# PL_DDR4.net
KiCad netlist of a schematic drawn in Altium Designer
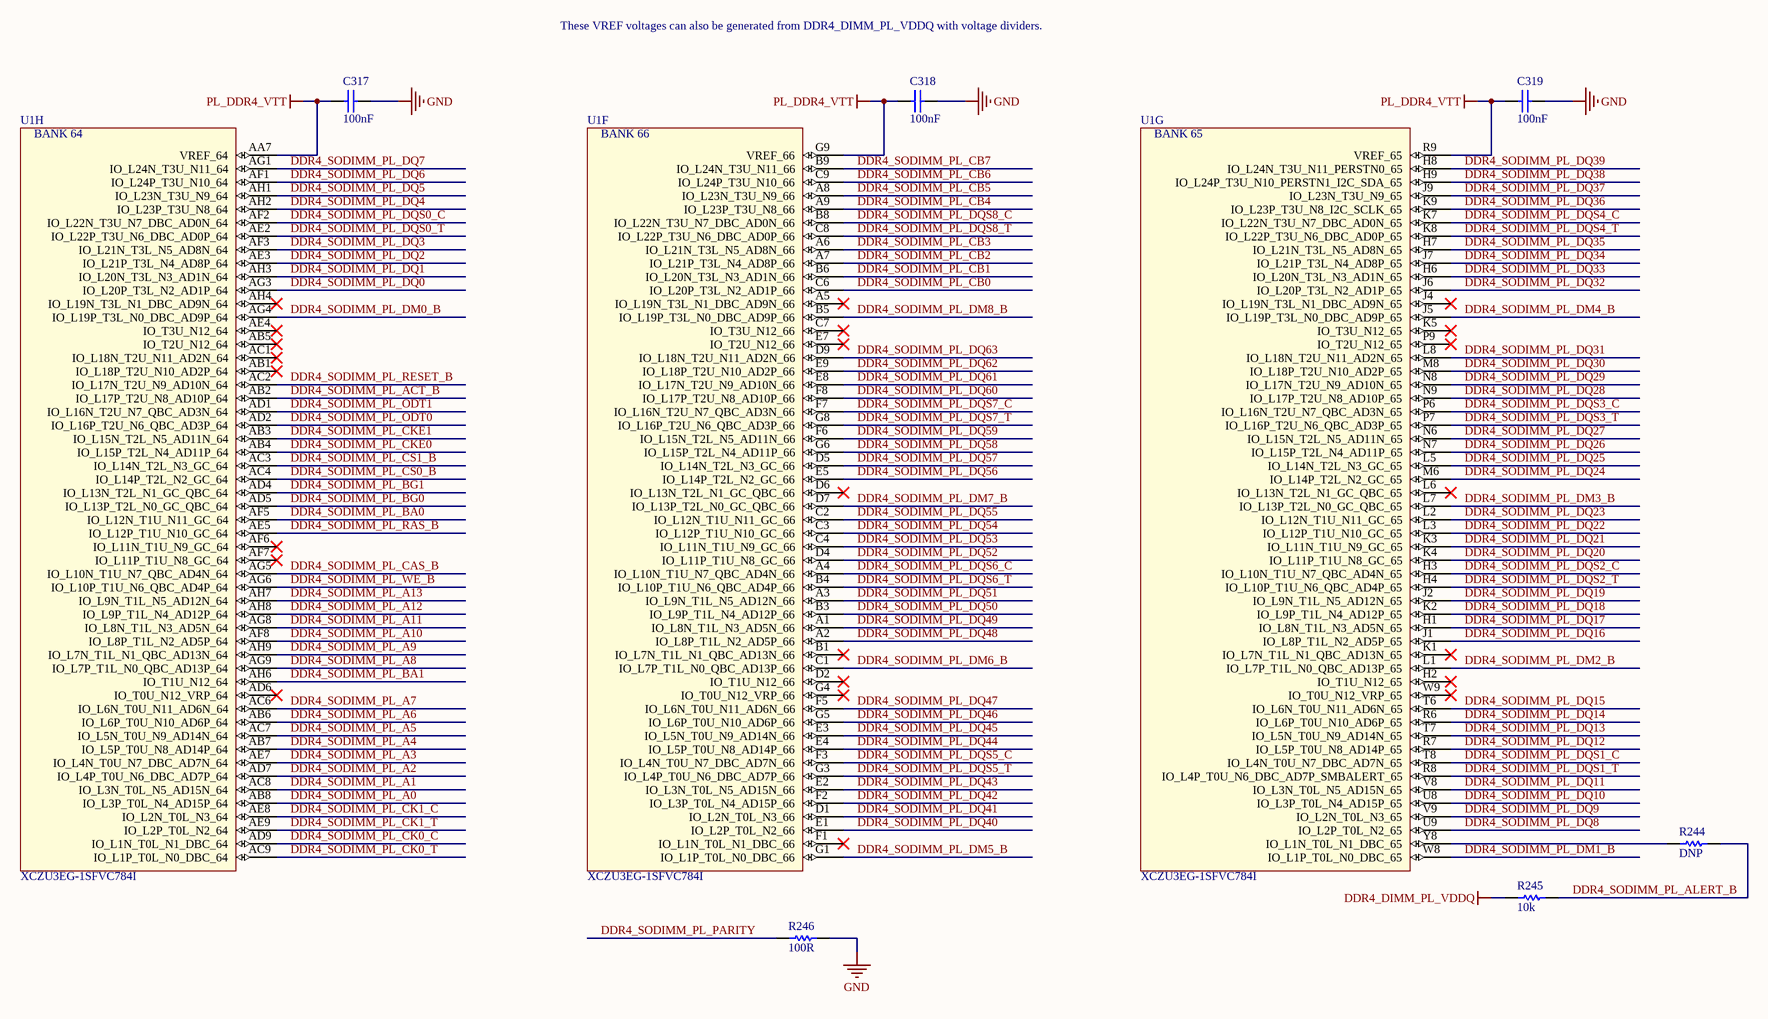
[diagram p0: PL_DDR4.SchDoc]

(export (version "E")
  (design (tool "Eeschema 10.0.6"))
  (components
    (comp (ref "C317")
      (value "100nF")
      (footprint "CAPC1005L_0402")
      (description "CAP CER 0.1UF 25V X7R 0402")
      (fields (field (name "VOLTAGE") "25V") (field (name "TOLERANCE") "10%"))
      (libsource (lib "Ultrascale_SchLib") (part "CAPCER0402X7R100N25V_10T"))
    )
    (comp (ref "C318")
      (value "100nF")
      (footprint "CAPC1005L_0402")
      (description "CAP CER 0.1UF 25V X7R 0402")
      (fields (field (name "VOLTAGE") "25V") (field (name "TOLERANCE") "10%"))
      (libsource (lib "Ultrascale_SchLib") (part "CAPCER0402X7R100N25V_10T"))
    )
    (comp (ref "C319")
      (value "100nF")
      (footprint "CAPC1005L_0402")
      (description "CAP CER 0.1UF 25V X7R 0402")
      (fields (field (name "VOLTAGE") "25V") (field (name "TOLERANCE") "10%"))
      (libsource (lib "Ultrascale_SchLib") (part "CAPCER0402X7R100N25V_10T"))
    )
    (comp (ref "R244")
      (value "DNP")
      (footprint "RESC1005L_0402")
      (description "RES SMD 0402 Footprint")
      (fields (field (name "Comment") "RES0402"))
      (libsource (lib "Ultrascale_SchLib") (part "RES0402"))
    )
    (comp (ref "R245")
      (value "10k")
      (footprint "RESC1005L_0402")
      (description "RES SMD 10K OHM 0.5% 1/16W 0402")
      (fields (field (name "POWER") "1/16W") (field (name "TOLERANCE") "0.5%"))
      (libsource (lib "Ultrascale_SchLib") (part "RES0402_10K_0W1_05T"))
    )
    (comp (ref "R246")
      (value "100R")
      (footprint "RESC1005L_0402")
      (description "RES SMD 100 OHM 1% 1/10W 0402")
      (fields (field (name "POWER") "1/10W") (field (name "TOLERANCE") "1%"))
      (libsource (lib "Ultrascale_SchLib") (part "RES0402_100R_0W1_1T"))
    )
    (comp (ref "U1")
      (value "XCZU3EG-1SFVC784I")
      (footprint "BGA784x28")
      (description "IC FPGA 252 I/O 784FCBGA - XILINX ZYNQ ULTRASCALE+")
      (libsource (lib "Ultrascale_SchLib") (part "XCZU3EG-1SFVC784I"))
    )
  )
  (nets
    (net (code "1") (name "/DDR4_SODIMM_PL_A0") (class "Default")
      (node (ref "U1") (pin "AB8") (pinfunction "IO_L3P_T0L_N4_AD15P_64_AB8") (pintype "bidirectional"))
    )
    (net (code "2") (name "/DDR4_SODIMM_PL_A1") (class "Default")
      (node (ref "U1") (pin "AC8") (pinfunction "IO_L3N_T0L_N5_AD15N_64_AC8") (pintype "bidirectional"))
    )
    (net (code "3") (name "/DDR4_SODIMM_PL_A2") (class "Default")
      (node (ref "U1") (pin "AD7") (pinfunction "IO_L4P_T0U_N6_DBC_AD7P_64_AD7") (pintype "bidirectional"))
    )
    (net (code "4") (name "/DDR4_SODIMM_PL_A3") (class "Default")
      (node (ref "U1") (pin "AE7") (pinfunction "IO_L4N_T0U_N7_DBC_AD7N_64_AE7") (pintype "bidirectional"))
    )
    (net (code "5") (name "/DDR4_SODIMM_PL_A4") (class "Default")
      (node (ref "U1") (pin "AB7") (pinfunction "IO_L5P_T0U_N8_AD14P_64_AB7") (pintype "bidirectional"))
    )
    (net (code "6") (name "/DDR4_SODIMM_PL_A5") (class "Default")
      (node (ref "U1") (pin "AC7") (pinfunction "IO_L5N_T0U_N9_AD14N_64_AC7") (pintype "bidirectional"))
    )
    (net (code "7") (name "/DDR4_SODIMM_PL_A6") (class "Default")
      (node (ref "U1") (pin "AB6") (pinfunction "IO_L6P_T0U_N10_AD6P_64_AB6") (pintype "bidirectional"))
    )
    (net (code "8") (name "/DDR4_SODIMM_PL_A7") (class "Default")
      (node (ref "U1") (pin "AC6") (pinfunction "IO_L6N_T0U_N11_AD6N_64_AC6") (pintype "bidirectional"))
    )
    (net (code "9") (name "/DDR4_SODIMM_PL_A8") (class "Default")
      (node (ref "U1") (pin "AG9") (pinfunction "IO_L7P_T1L_N0_QBC_AD13P_64_AG9") (pintype "bidirectional"))
    )
    (net (code "10") (name "/DDR4_SODIMM_PL_A9") (class "Default")
      (node (ref "U1") (pin "AH9") (pinfunction "IO_L7N_T1L_N1_QBC_AD13N_64_AH9") (pintype "bidirectional"))
    )
    (net (code "11") (name "/DDR4_SODIMM_PL_A10") (class "Default")
      (node (ref "U1") (pin "AF8") (pinfunction "IO_L8P_T1L_N2_AD5P_64_AF8") (pintype "bidirectional"))
    )
    (net (code "12") (name "/DDR4_SODIMM_PL_A11") (class "Default")
      (node (ref "U1") (pin "AG8") (pinfunction "IO_L8N_T1L_N3_AD5N_64_AG8") (pintype "bidirectional"))
    )
    (net (code "13") (name "/DDR4_SODIMM_PL_A12") (class "Default")
      (node (ref "U1") (pin "AH8") (pinfunction "IO_L9P_T1L_N4_AD12P_64_AH8") (pintype "bidirectional"))
    )
    (net (code "14") (name "/DDR4_SODIMM_PL_A13") (class "Default")
      (node (ref "U1") (pin "AH7") (pinfunction "IO_L9N_T1L_N5_AD12N_64_AH7") (pintype "bidirectional"))
    )
    (net (code "15") (name "/DDR4_SODIMM_PL_ACT_B") (class "Default")
      (node (ref "U1") (pin "AB2") (pinfunction "IO_L17P_T2U_N8_AD10P_64_AB2") (pintype "bidirectional"))
    )
    (net (code "16") (name "/DDR4_SODIMM_PL_ALERT_B") (class "Default")
      (node (ref "R244") (pin "2") (pinfunction "2_2") (pintype "passive"))
      (node (ref "R245") (pin "1") (pinfunction "1_1") (pintype "passive"))
    )
    (net (code "17") (name "/DDR4_SODIMM_PL_BA0") (class "Default")
      (node (ref "U1") (pin "AF5") (pinfunction "IO_L12N_T1U_N11_GC_64_AF5") (pintype "bidirectional"))
    )
    (net (code "18") (name "/DDR4_SODIMM_PL_BA1") (class "Default")
      (node (ref "U1") (pin "AH6") (pinfunction "IO_T1U_N12_64_AH6") (pintype "bidirectional"))
    )
    (net (code "19") (name "/DDR4_SODIMM_PL_BG0") (class "Default")
      (node (ref "U1") (pin "AD5") (pinfunction "IO_L13P_T2L_N0_GC_QBC_64_AD5") (pintype "bidirectional"))
    )
    (net (code "20") (name "/DDR4_SODIMM_PL_BG1") (class "Default")
      (node (ref "U1") (pin "AD4") (pinfunction "IO_L13N_T2L_N1_GC_QBC_64_AD4") (pintype "bidirectional"))
    )
    (net (code "21") (name "/DDR4_SODIMM_PL_CAS_B") (class "Default")
      (node (ref "U1") (pin "AG5") (pinfunction "IO_L10N_T1U_N7_QBC_AD4N_64_AG5") (pintype "bidirectional"))
    )
    (net (code "22") (name "/DDR4_SODIMM_PL_CB0") (class "Default")
      (node (ref "U1") (pin "C6") (pinfunction "IO_L20P_T3L_N2_AD1P_66_C6") (pintype "bidirectional"))
    )
    (net (code "23") (name "/DDR4_SODIMM_PL_CB1") (class "Default")
      (node (ref "U1") (pin "B6") (pinfunction "IO_L20N_T3L_N3_AD1N_66_B6") (pintype "bidirectional"))
    )
    (net (code "24") (name "/DDR4_SODIMM_PL_CB2") (class "Default")
      (node (ref "U1") (pin "A7") (pinfunction "IO_L21P_T3L_N4_AD8P_66_A7") (pintype "bidirectional"))
    )
    (net (code "25") (name "/DDR4_SODIMM_PL_CB3") (class "Default")
      (node (ref "U1") (pin "A6") (pinfunction "IO_L21N_T3L_N5_AD8N_66_A6") (pintype "bidirectional"))
    )
    (net (code "26") (name "/DDR4_SODIMM_PL_CB4") (class "Default")
      (node (ref "U1") (pin "A9") (pinfunction "IO_L23P_T3U_N8_66_A9") (pintype "bidirectional"))
    )
    (net (code "27") (name "/DDR4_SODIMM_PL_CB5") (class "Default")
      (node (ref "U1") (pin "A8") (pinfunction "IO_L23N_T3U_N9_66_A8") (pintype "bidirectional"))
    )
    (net (code "28") (name "/DDR4_SODIMM_PL_CB6") (class "Default")
      (node (ref "U1") (pin "C9") (pinfunction "IO_L24P_T3U_N10_66_C9") (pintype "bidirectional"))
    )
    (net (code "29") (name "/DDR4_SODIMM_PL_CB7") (class "Default")
      (node (ref "U1") (pin "B9") (pinfunction "IO_L24N_T3U_N11_66_B9") (pintype "bidirectional"))
    )
    (net (code "30") (name "/DDR4_SODIMM_PL_CK0_C") (class "Default")
      (node (ref "U1") (pin "AD9") (pinfunction "IO_L1N_T0L_N1_DBC_64_AD9") (pintype "bidirectional"))
    )
    (net (code "31") (name "/DDR4_SODIMM_PL_CK0_T") (class "Default")
      (node (ref "U1") (pin "AC9") (pinfunction "IO_L1P_T0L_N0_DBC_64_AC9") (pintype "bidirectional"))
    )
    (net (code "32") (name "/DDR4_SODIMM_PL_CK1_C") (class "Default")
      (node (ref "U1") (pin "AE8") (pinfunction "IO_L2N_T0L_N3_64_AE8") (pintype "bidirectional"))
    )
    (net (code "33") (name "/DDR4_SODIMM_PL_CK1_T") (class "Default")
      (node (ref "U1") (pin "AE9") (pinfunction "IO_L2P_T0L_N2_64_AE9") (pintype "bidirectional"))
    )
    (net (code "34") (name "/DDR4_SODIMM_PL_CKE0") (class "Default")
      (node (ref "U1") (pin "AB4") (pinfunction "IO_L15P_T2L_N4_AD11P_64_AB4") (pintype "bidirectional"))
    )
    (net (code "35") (name "/DDR4_SODIMM_PL_CKE1") (class "Default")
      (node (ref "U1") (pin "AB3") (pinfunction "IO_L15N_T2L_N5_AD11N_64_AB3") (pintype "bidirectional"))
    )
    (net (code "36") (name "/DDR4_SODIMM_PL_CS0_B") (class "Default")
      (node (ref "U1") (pin "AC4") (pinfunction "IO_L14P_T2L_N2_GC_64_AC4") (pintype "bidirectional"))
    )
    (net (code "37") (name "/DDR4_SODIMM_PL_CS1_B") (class "Default")
      (node (ref "U1") (pin "AC3") (pinfunction "IO_L14N_T2L_N3_GC_64_AC3") (pintype "bidirectional"))
    )
    (net (code "38") (name "/DDR4_SODIMM_PL_DM0_B") (class "Default")
      (node (ref "U1") (pin "AG4") (pinfunction "IO_L19P_T3L_N0_DBC_AD9P_64_AG4") (pintype "bidirectional"))
    )
    (net (code "39") (name "/DDR4_SODIMM_PL_DM1_B") (class "Default")
      (node (ref "U1") (pin "W8") (pinfunction "IO_L1P_T0L_N0_DBC_65_W8") (pintype "bidirectional"))
    )
    (net (code "40") (name "/DDR4_SODIMM_PL_DM2_B") (class "Default")
      (node (ref "U1") (pin "L1") (pinfunction "IO_L7P_T1L_N0_QBC_AD13P_65_L1") (pintype "bidirectional"))
    )
    (net (code "41") (name "/DDR4_SODIMM_PL_DM3_B") (class "Default")
      (node (ref "U1") (pin "L7") (pinfunction "IO_L13P_T2L_N0_GC_QBC_65_L7") (pintype "bidirectional"))
    )
    (net (code "42") (name "/DDR4_SODIMM_PL_DM4_B") (class "Default")
      (node (ref "U1") (pin "J5") (pinfunction "IO_L19P_T3L_N0_DBC_AD9P_65_J5") (pintype "bidirectional"))
    )
    (net (code "43") (name "/DDR4_SODIMM_PL_DM5_B") (class "Default")
      (node (ref "U1") (pin "G1") (pinfunction "IO_L1P_T0L_N0_DBC_66_G1") (pintype "bidirectional"))
    )
    (net (code "44") (name "/DDR4_SODIMM_PL_DM6_B") (class "Default")
      (node (ref "U1") (pin "C1") (pinfunction "IO_L7P_T1L_N0_QBC_AD13P_66_C1") (pintype "bidirectional"))
    )
    (net (code "45") (name "/DDR4_SODIMM_PL_DM7_B") (class "Default")
      (node (ref "U1") (pin "D7") (pinfunction "IO_L13P_T2L_N0_GC_QBC_66_D7") (pintype "bidirectional"))
    )
    (net (code "46") (name "/DDR4_SODIMM_PL_DM8_B") (class "Default")
      (node (ref "U1") (pin "B5") (pinfunction "IO_L19P_T3L_N0_DBC_AD9P_66_B5") (pintype "bidirectional"))
    )
    (net (code "47") (name "/DDR4_SODIMM_PL_DQ0") (class "Default")
      (node (ref "U1") (pin "AG3") (pinfunction "IO_L20P_T3L_N2_AD1P_64_AG3") (pintype "bidirectional"))
    )
    (net (code "48") (name "/DDR4_SODIMM_PL_DQ1") (class "Default")
      (node (ref "U1") (pin "AH3") (pinfunction "IO_L20N_T3L_N3_AD1N_64_AH3") (pintype "bidirectional"))
    )
    (net (code "49") (name "/DDR4_SODIMM_PL_DQ2") (class "Default")
      (node (ref "U1") (pin "AE3") (pinfunction "IO_L21P_T3L_N4_AD8P_64_AE3") (pintype "bidirectional"))
    )
    (net (code "50") (name "/DDR4_SODIMM_PL_DQ3") (class "Default")
      (node (ref "U1") (pin "AF3") (pinfunction "IO_L21N_T3L_N5_AD8N_64_AF3") (pintype "bidirectional"))
    )
    (net (code "51") (name "/DDR4_SODIMM_PL_DQ4") (class "Default")
      (node (ref "U1") (pin "AH2") (pinfunction "IO_L23P_T3U_N8_64_AH2") (pintype "bidirectional"))
    )
    (net (code "52") (name "/DDR4_SODIMM_PL_DQ5") (class "Default")
      (node (ref "U1") (pin "AH1") (pinfunction "IO_L23N_T3U_N9_64_AH1") (pintype "bidirectional"))
    )
    (net (code "53") (name "/DDR4_SODIMM_PL_DQ6") (class "Default")
      (node (ref "U1") (pin "AF1") (pinfunction "IO_L24P_T3U_N10_64_AF1") (pintype "bidirectional"))
    )
    (net (code "54") (name "/DDR4_SODIMM_PL_DQ7") (class "Default")
      (node (ref "U1") (pin "AG1") (pinfunction "IO_L24N_T3U_N11_64_AG1") (pintype "bidirectional"))
    )
    (net (code "55") (name "/DDR4_SODIMM_PL_DQ8") (class "Default")
      (node (ref "U1") (pin "U9") (pinfunction "IO_L2P_T0L_N2_65_U9") (pintype "bidirectional"))
    )
    (net (code "56") (name "/DDR4_SODIMM_PL_DQ9") (class "Default")
      (node (ref "U1") (pin "V9") (pinfunction "IO_L2N_T0L_N3_65_V9") (pintype "bidirectional"))
    )
    (net (code "57") (name "/DDR4_SODIMM_PL_DQ10") (class "Default")
      (node (ref "U1") (pin "U8") (pinfunction "IO_L3P_T0L_N4_AD15P_65_U8") (pintype "bidirectional"))
    )
    (net (code "58") (name "/DDR4_SODIMM_PL_DQ11") (class "Default")
      (node (ref "U1") (pin "V8") (pinfunction "IO_L3N_T0L_N5_AD15N_65_V8") (pintype "bidirectional"))
    )
    (net (code "59") (name "/DDR4_SODIMM_PL_DQ12") (class "Default")
      (node (ref "U1") (pin "R7") (pinfunction "IO_L5P_T0U_N8_AD14P_65_R7") (pintype "bidirectional"))
    )
    (net (code "60") (name "/DDR4_SODIMM_PL_DQ13") (class "Default")
      (node (ref "U1") (pin "T7") (pinfunction "IO_L5N_T0U_N9_AD14N_65_T7") (pintype "bidirectional"))
    )
    (net (code "61") (name "/DDR4_SODIMM_PL_DQ14") (class "Default")
      (node (ref "U1") (pin "R6") (pinfunction "IO_L6P_T0U_N10_AD6P_65_R6") (pintype "bidirectional"))
    )
    (net (code "62") (name "/DDR4_SODIMM_PL_DQ15") (class "Default")
      (node (ref "U1") (pin "T6") (pinfunction "IO_L6N_T0U_N11_AD6N_65_T6") (pintype "bidirectional"))
    )
    (net (code "63") (name "/DDR4_SODIMM_PL_DQ16") (class "Default")
      (node (ref "U1") (pin "J1") (pinfunction "IO_L8P_T1L_N2_AD5P_65_J1") (pintype "bidirectional"))
    )
    (net (code "64") (name "/DDR4_SODIMM_PL_DQ17") (class "Default")
      (node (ref "U1") (pin "H1") (pinfunction "IO_L8N_T1L_N3_AD5N_65_H1") (pintype "bidirectional"))
    )
    (net (code "65") (name "/DDR4_SODIMM_PL_DQ18") (class "Default")
      (node (ref "U1") (pin "K2") (pinfunction "IO_L9P_T1L_N4_AD12P_65_K2") (pintype "bidirectional"))
    )
    (net (code "66") (name "/DDR4_SODIMM_PL_DQ19") (class "Default")
      (node (ref "U1") (pin "J2") (pinfunction "IO_L9N_T1L_N5_AD12N_65_J2") (pintype "bidirectional"))
    )
    (net (code "67") (name "/DDR4_SODIMM_PL_DQ20") (class "Default")
      (node (ref "U1") (pin "K4") (pinfunction "IO_L11P_T1U_N8_GC_65_K4") (pintype "bidirectional"))
    )
    (net (code "68") (name "/DDR4_SODIMM_PL_DQ21") (class "Default")
      (node (ref "U1") (pin "K3") (pinfunction "IO_L11N_T1U_N9_GC_65_K3") (pintype "bidirectional"))
    )
    (net (code "69") (name "/DDR4_SODIMM_PL_DQ22") (class "Default")
      (node (ref "U1") (pin "L3") (pinfunction "IO_L12P_T1U_N10_GC_65_L3") (pintype "bidirectional"))
    )
    (net (code "70") (name "/DDR4_SODIMM_PL_DQ23") (class "Default")
      (node (ref "U1") (pin "L2") (pinfunction "IO_L12N_T1U_N11_GC_65_L2") (pintype "bidirectional"))
    )
    (net (code "71") (name "/DDR4_SODIMM_PL_DQ24") (class "Default")
      (node (ref "U1") (pin "M6") (pinfunction "IO_L14P_T2L_N2_GC_65_M6") (pintype "bidirectional"))
    )
    (net (code "72") (name "/DDR4_SODIMM_PL_DQ25") (class "Default")
      (node (ref "U1") (pin "L5") (pinfunction "IO_L14N_T2L_N3_GC_65_L5") (pintype "bidirectional"))
    )
    (net (code "73") (name "/DDR4_SODIMM_PL_DQ26") (class "Default")
      (node (ref "U1") (pin "N7") (pinfunction "IO_L15P_T2L_N4_AD11P_65_N7") (pintype "bidirectional"))
    )
    (net (code "74") (name "/DDR4_SODIMM_PL_DQ27") (class "Default")
      (node (ref "U1") (pin "N6") (pinfunction "IO_L15N_T2L_N5_AD11N_65_N6") (pintype "bidirectional"))
    )
    (net (code "75") (name "/DDR4_SODIMM_PL_DQ28") (class "Default")
      (node (ref "U1") (pin "N9") (pinfunction "IO_L17P_T2U_N8_AD10P_65_N9") (pintype "bidirectional"))
    )
    (net (code "76") (name "/DDR4_SODIMM_PL_DQ29") (class "Default")
      (node (ref "U1") (pin "N8") (pinfunction "IO_L17N_T2U_N9_AD10N_65_N8") (pintype "bidirectional"))
    )
    (net (code "77") (name "/DDR4_SODIMM_PL_DQ30") (class "Default")
      (node (ref "U1") (pin "M8") (pinfunction "IO_L18P_T2U_N10_AD2P_65_M8") (pintype "bidirectional"))
    )
    (net (code "78") (name "/DDR4_SODIMM_PL_DQ31") (class "Default")
      (node (ref "U1") (pin "L8") (pinfunction "IO_L18N_T2U_N11_AD2N_65_L8") (pintype "bidirectional"))
    )
    (net (code "79") (name "/DDR4_SODIMM_PL_DQ32") (class "Default")
      (node (ref "U1") (pin "J6") (pinfunction "IO_L20P_T3L_N2_AD1P_65_J6") (pintype "bidirectional"))
    )
    (net (code "80") (name "/DDR4_SODIMM_PL_DQ33") (class "Default")
      (node (ref "U1") (pin "H6") (pinfunction "IO_L20N_T3L_N3_AD1N_65_H6") (pintype "bidirectional"))
    )
    (net (code "81") (name "/DDR4_SODIMM_PL_DQ34") (class "Default")
      (node (ref "U1") (pin "J7") (pinfunction "IO_L21P_T3L_N4_AD8P_65_J7") (pintype "bidirectional"))
    )
    (net (code "82") (name "/DDR4_SODIMM_PL_DQ35") (class "Default")
      (node (ref "U1") (pin "H7") (pinfunction "IO_L21N_T3L_N5_AD8N_65_H7") (pintype "bidirectional"))
    )
    (net (code "83") (name "/DDR4_SODIMM_PL_DQ36") (class "Default")
      (node (ref "U1") (pin "K9") (pinfunction "IO_L23P_T3U_N8_I2C_SCLK_65_K9") (pintype "bidirectional"))
    )
    (net (code "84") (name "/DDR4_SODIMM_PL_DQ37") (class "Default")
      (node (ref "U1") (pin "J9") (pinfunction "IO_L23N_T3U_N9_65_J9") (pintype "bidirectional"))
    )
    (net (code "85") (name "/DDR4_SODIMM_PL_DQ38") (class "Default")
      (node (ref "U1") (pin "H9") (pinfunction "IO_L24P_T3U_N10_PERSTN1_I2C_SDA_65_H9") (pintype "bidirectional"))
    )
    (net (code "86") (name "/DDR4_SODIMM_PL_DQ39") (class "Default")
      (node (ref "U1") (pin "H8") (pinfunction "IO_L24N_T3U_N11_PERSTN0_65_H8") (pintype "bidirectional"))
    )
    (net (code "87") (name "/DDR4_SODIMM_PL_DQ40") (class "Default")
      (node (ref "U1") (pin "E1") (pinfunction "IO_L2P_T0L_N2_66_E1") (pintype "bidirectional"))
    )
    (net (code "88") (name "/DDR4_SODIMM_PL_DQ41") (class "Default")
      (node (ref "U1") (pin "D1") (pinfunction "IO_L2N_T0L_N3_66_D1") (pintype "bidirectional"))
    )
    (net (code "89") (name "/DDR4_SODIMM_PL_DQ42") (class "Default")
      (node (ref "U1") (pin "F2") (pinfunction "IO_L3P_T0L_N4_AD15P_66_F2") (pintype "bidirectional"))
    )
    (net (code "90") (name "/DDR4_SODIMM_PL_DQ43") (class "Default")
      (node (ref "U1") (pin "E2") (pinfunction "IO_L3N_T0L_N5_AD15N_66_E2") (pintype "bidirectional"))
    )
    (net (code "91") (name "/DDR4_SODIMM_PL_DQ44") (class "Default")
      (node (ref "U1") (pin "E4") (pinfunction "IO_L5P_T0U_N8_AD14P_66_E4") (pintype "bidirectional"))
    )
    (net (code "92") (name "/DDR4_SODIMM_PL_DQ45") (class "Default")
      (node (ref "U1") (pin "E3") (pinfunction "IO_L5N_T0U_N9_AD14N_66_E3") (pintype "bidirectional"))
    )
    (net (code "93") (name "/DDR4_SODIMM_PL_DQ46") (class "Default")
      (node (ref "U1") (pin "G5") (pinfunction "IO_L6P_T0U_N10_AD6P_66_G5") (pintype "bidirectional"))
    )
    (net (code "94") (name "/DDR4_SODIMM_PL_DQ47") (class "Default")
      (node (ref "U1") (pin "F5") (pinfunction "IO_L6N_T0U_N11_AD6N_66_F5") (pintype "bidirectional"))
    )
    (net (code "95") (name "/DDR4_SODIMM_PL_DQ48") (class "Default")
      (node (ref "U1") (pin "A2") (pinfunction "IO_L8P_T1L_N2_AD5P_66_A2") (pintype "bidirectional"))
    )
    (net (code "96") (name "/DDR4_SODIMM_PL_DQ49") (class "Default")
      (node (ref "U1") (pin "A1") (pinfunction "IO_L8N_T1L_N3_AD5N_66_A1") (pintype "bidirectional"))
    )
    (net (code "97") (name "/DDR4_SODIMM_PL_DQ50") (class "Default")
      (node (ref "U1") (pin "B3") (pinfunction "IO_L9P_T1L_N4_AD12P_66_B3") (pintype "bidirectional"))
    )
    (net (code "98") (name "/DDR4_SODIMM_PL_DQ51") (class "Default")
      (node (ref "U1") (pin "A3") (pinfunction "IO_L9N_T1L_N5_AD12N_66_A3") (pintype "bidirectional"))
    )
    (net (code "99") (name "/DDR4_SODIMM_PL_DQ52") (class "Default")
      (node (ref "U1") (pin "D4") (pinfunction "IO_L11P_T1U_N8_GC_66_D4") (pintype "bidirectional"))
    )
    (net (code "100") (name "/DDR4_SODIMM_PL_DQ53") (class "Default")
      (node (ref "U1") (pin "C4") (pinfunction "IO_L11N_T1U_N9_GC_66_C4") (pintype "bidirectional"))
    )
    (net (code "101") (name "/DDR4_SODIMM_PL_DQ54") (class "Default")
      (node (ref "U1") (pin "C3") (pinfunction "IO_L12P_T1U_N10_GC_66_C3") (pintype "bidirectional"))
    )
    (net (code "102") (name "/DDR4_SODIMM_PL_DQ55") (class "Default")
      (node (ref "U1") (pin "C2") (pinfunction "IO_L12N_T1U_N11_GC_66_C2") (pintype "bidirectional"))
    )
    (net (code "103") (name "/DDR4_SODIMM_PL_DQ56") (class "Default")
      (node (ref "U1") (pin "E5") (pinfunction "IO_L14P_T2L_N2_GC_66_E5") (pintype "bidirectional"))
    )
    (net (code "104") (name "/DDR4_SODIMM_PL_DQ57") (class "Default")
      (node (ref "U1") (pin "D5") (pinfunction "IO_L14N_T2L_N3_GC_66_D5") (pintype "bidirectional"))
    )
    (net (code "105") (name "/DDR4_SODIMM_PL_DQ58") (class "Default")
      (node (ref "U1") (pin "G6") (pinfunction "IO_L15P_T2L_N4_AD11P_66_G6") (pintype "bidirectional"))
    )
    (net (code "106") (name "/DDR4_SODIMM_PL_DQ59") (class "Default")
      (node (ref "U1") (pin "F6") (pinfunction "IO_L15N_T2L_N5_AD11N_66_F6") (pintype "bidirectional"))
    )
    (net (code "107") (name "/DDR4_SODIMM_PL_DQ60") (class "Default")
      (node (ref "U1") (pin "F8") (pinfunction "IO_L17P_T2U_N8_AD10P_66_F8") (pintype "bidirectional"))
    )
    (net (code "108") (name "/DDR4_SODIMM_PL_DQ61") (class "Default")
      (node (ref "U1") (pin "E8") (pinfunction "IO_L17N_T2U_N9_AD10N_66_E8") (pintype "bidirectional"))
    )
    (net (code "109") (name "/DDR4_SODIMM_PL_DQ62") (class "Default")
      (node (ref "U1") (pin "E9") (pinfunction "IO_L18P_T2U_N10_AD2P_66_E9") (pintype "bidirectional"))
    )
    (net (code "110") (name "/DDR4_SODIMM_PL_DQ63") (class "Default")
      (node (ref "U1") (pin "D9") (pinfunction "IO_L18N_T2U_N11_AD2N_66_D9") (pintype "bidirectional"))
    )
    (net (code "111") (name "/DDR4_SODIMM_PL_DQS0_C") (class "Default")
      (node (ref "U1") (pin "AF2") (pinfunction "IO_L22N_T3U_N7_DBC_AD0N_64_AF2") (pintype "bidirectional"))
    )
    (net (code "112") (name "/DDR4_SODIMM_PL_DQS0_T") (class "Default")
      (node (ref "U1") (pin "AE2") (pinfunction "IO_L22P_T3U_N6_DBC_AD0P_64_AE2") (pintype "bidirectional"))
    )
    (net (code "113") (name "/DDR4_SODIMM_PL_DQS1_C") (class "Default")
      (node (ref "U1") (pin "T8") (pinfunction "IO_L4N_T0U_N7_DBC_AD7N_65_T8") (pintype "bidirectional"))
    )
    (net (code "114") (name "/DDR4_SODIMM_PL_DQS1_T") (class "Default")
      (node (ref "U1") (pin "R8") (pinfunction "IO_L4P_T0U_N6_DBC_AD7P_SMBALERT_65_R8") (pintype "bidirectional"))
    )
    (net (code "115") (name "/DDR4_SODIMM_PL_DQS2_C") (class "Default")
      (node (ref "U1") (pin "H3") (pinfunction "IO_L10N_T1U_N7_QBC_AD4N_65_H3") (pintype "bidirectional"))
    )
    (net (code "116") (name "/DDR4_SODIMM_PL_DQS2_T") (class "Default")
      (node (ref "U1") (pin "H4") (pinfunction "IO_L10P_T1U_N6_QBC_AD4P_65_H4") (pintype "bidirectional"))
    )
    (net (code "117") (name "/DDR4_SODIMM_PL_DQS3_C") (class "Default")
      (node (ref "U1") (pin "P6") (pinfunction "IO_L16N_T2U_N7_QBC_AD3N_65_P6") (pintype "bidirectional"))
    )
    (net (code "118") (name "/DDR4_SODIMM_PL_DQS3_T") (class "Default")
      (node (ref "U1") (pin "P7") (pinfunction "IO_L16P_T2U_N6_QBC_AD3P_65_P7") (pintype "bidirectional"))
    )
    (net (code "119") (name "/DDR4_SODIMM_PL_DQS4_C") (class "Default")
      (node (ref "U1") (pin "K7") (pinfunction "IO_L22N_T3U_N7_DBC_AD0N_65_K7") (pintype "bidirectional"))
    )
    (net (code "120") (name "/DDR4_SODIMM_PL_DQS4_T") (class "Default")
      (node (ref "U1") (pin "K8") (pinfunction "IO_L22P_T3U_N6_DBC_AD0P_65_K8") (pintype "bidirectional"))
    )
    (net (code "121") (name "/DDR4_SODIMM_PL_DQS5_C") (class "Default")
      (node (ref "U1") (pin "F3") (pinfunction "IO_L4N_T0U_N7_DBC_AD7N_66_F3") (pintype "bidirectional"))
    )
    (net (code "122") (name "/DDR4_SODIMM_PL_DQS5_T") (class "Default")
      (node (ref "U1") (pin "G3") (pinfunction "IO_L4P_T0U_N6_DBC_AD7P_66_G3") (pintype "bidirectional"))
    )
    (net (code "123") (name "/DDR4_SODIMM_PL_DQS6_C") (class "Default")
      (node (ref "U1") (pin "A4") (pinfunction "IO_L10N_T1U_N7_QBC_AD4N_66_A4") (pintype "bidirectional"))
    )
    (net (code "124") (name "/DDR4_SODIMM_PL_DQS6_T") (class "Default")
      (node (ref "U1") (pin "B4") (pinfunction "IO_L10P_T1U_N6_QBC_AD4P_66_B4") (pintype "bidirectional"))
    )
    (net (code "125") (name "/DDR4_SODIMM_PL_DQS7_C") (class "Default")
      (node (ref "U1") (pin "F7") (pinfunction "IO_L16N_T2U_N7_QBC_AD3N_66_F7") (pintype "bidirectional"))
    )
    (net (code "126") (name "/DDR4_SODIMM_PL_DQS7_T") (class "Default")
      (node (ref "U1") (pin "G8") (pinfunction "IO_L16P_T2U_N6_QBC_AD3P_66_G8") (pintype "bidirectional"))
    )
    (net (code "127") (name "/DDR4_SODIMM_PL_DQS8_C") (class "Default")
      (node (ref "U1") (pin "B8") (pinfunction "IO_L22N_T3U_N7_DBC_AD0N_66_B8") (pintype "bidirectional"))
    )
    (net (code "128") (name "/DDR4_SODIMM_PL_DQS8_T") (class "Default")
      (node (ref "U1") (pin "C8") (pinfunction "IO_L22P_T3U_N6_DBC_AD0P_66_C8") (pintype "bidirectional"))
    )
    (net (code "129") (name "/DDR4_SODIMM_PL_ODT0") (class "Default")
      (node (ref "U1") (pin "AD2") (pinfunction "IO_L16P_T2U_N6_QBC_AD3P_64_AD2") (pintype "bidirectional"))
    )
    (net (code "130") (name "/DDR4_SODIMM_PL_ODT1") (class "Default")
      (node (ref "U1") (pin "AD1") (pinfunction "IO_L16N_T2U_N7_QBC_AD3N_64_AD1") (pintype "bidirectional"))
    )
    (net (code "131") (name "/DDR4_SODIMM_PL_PARITY") (class "Default")
      (node (ref "R246") (pin "1") (pinfunction "1_1") (pintype "passive"))
    )
    (net (code "132") (name "/DDR4_SODIMM_PL_RAS_B") (class "Default")
      (node (ref "U1") (pin "AE5") (pinfunction "IO_L12P_T1U_N10_GC_64_AE5") (pintype "bidirectional"))
    )
    (net (code "133") (name "/DDR4_SODIMM_PL_RESET_B") (class "Default")
      (node (ref "U1") (pin "AC2") (pinfunction "IO_L17N_T2U_N9_AD10N_64_AC2") (pintype "bidirectional"))
    )
    (net (code "134") (name "/DDR4_SODIMM_PL_WE_B") (class "Default")
      (node (ref "U1") (pin "AG6") (pinfunction "IO_L10P_T1U_N6_QBC_AD4P_64_AG6") (pintype "bidirectional"))
    )
    (net (code "135") (name "DDR4_DIMM_PL_VDDQ") (class "Default")
      (node (ref "R245") (pin "2") (pinfunction "2_2") (pintype "passive"))
    )
    (net (code "136") (name "GND") (class "Default")
      (node (ref "C317") (pin "1") (pinfunction "1_1") (pintype "passive"))
      (node (ref "C318") (pin "1") (pinfunction "1_1") (pintype "passive"))
      (node (ref "C319") (pin "1") (pinfunction "1_1") (pintype "passive"))
      (node (ref "R246") (pin "2") (pinfunction "2_2") (pintype "passive"))
    )
    (net (code "137") (name "Net-(U1G-IO_L1N_T0L_N1_DBC_65)") (class "Default")
      (node (ref "R244") (pin "1") (pinfunction "1_1") (pintype "passive"))
      (node (ref "U1") (pin "Y8") (pinfunction "IO_L1N_T0L_N1_DBC_65_Y8") (pintype "bidirectional"))
    )
    (net (code "138") (name "PL_DDR4_VTT") (class "Default")
      (node (ref "C317") (pin "2") (pinfunction "2_2") (pintype "passive"))
      (node (ref "C318") (pin "2") (pinfunction "2_2") (pintype "passive"))
      (node (ref "C319") (pin "2") (pinfunction "2_2") (pintype "passive"))
      (node (ref "U1") (pin "AA7") (pinfunction "VREF_64_AA7") (pintype "bidirectional"))
      (node (ref "U1") (pin "G9") (pinfunction "VREF_66_G9") (pintype "bidirectional"))
      (node (ref "U1") (pin "R9") (pinfunction "VREF_65_R9") (pintype "bidirectional"))
    )
    (net (code "139") (name "unconnected-(U1F-IO_L1N_T0L_N1_DBC_66-PadF1)") (class "Default")
      (node (ref "U1") (pin "F1") (pinfunction "IO_L1N_T0L_N1_DBC_66_F1") (pintype "bidirectional+no_connect"))
    )
    (net (code "140") (name "unconnected-(U1F-IO_L7N_T1L_N1_QBC_AD13N_66-PadB1)") (class "Default")
      (node (ref "U1") (pin "B1") (pinfunction "IO_L7N_T1L_N1_QBC_AD13N_66_B1") (pintype "bidirectional+no_connect"))
    )
    (net (code "141") (name "unconnected-(U1F-IO_L13N_T2L_N1_GC_QBC_66-PadD6)") (class "Default")
      (node (ref "U1") (pin "D6") (pinfunction "IO_L13N_T2L_N1_GC_QBC_66_D6") (pintype "bidirectional+no_connect"))
    )
    (net (code "142") (name "unconnected-(U1F-IO_L19N_T3L_N1_DBC_AD9N_66-PadA5)") (class "Default")
      (node (ref "U1") (pin "A5") (pinfunction "IO_L19N_T3L_N1_DBC_AD9N_66_A5") (pintype "bidirectional+no_connect"))
    )
    (net (code "143") (name "unconnected-(U1F-IO_T0U_N12_VRP_66-PadG4)") (class "Default")
      (node (ref "U1") (pin "G4") (pinfunction "IO_T0U_N12_VRP_66_G4") (pintype "bidirectional+no_connect"))
    )
    (net (code "144") (name "unconnected-(U1F-IO_T1U_N12_66-PadD2)") (class "Default")
      (node (ref "U1") (pin "D2") (pinfunction "IO_T1U_N12_66_D2") (pintype "bidirectional+no_connect"))
    )
    (net (code "145") (name "unconnected-(U1F-IO_T2U_N12_66-PadE7)") (class "Default")
      (node (ref "U1") (pin "E7") (pinfunction "IO_T2U_N12_66_E7") (pintype "bidirectional+no_connect"))
    )
    (net (code "146") (name "unconnected-(U1F-IO_T3U_N12_66-PadC7)") (class "Default")
      (node (ref "U1") (pin "C7") (pinfunction "IO_T3U_N12_66_C7") (pintype "bidirectional+no_connect"))
    )
    (net (code "147") (name "unconnected-(U1G-IO_L7N_T1L_N1_QBC_AD13N_65-PadK1)") (class "Default")
      (node (ref "U1") (pin "K1") (pinfunction "IO_L7N_T1L_N1_QBC_AD13N_65_K1") (pintype "bidirectional+no_connect"))
    )
    (net (code "148") (name "unconnected-(U1G-IO_L13N_T2L_N1_GC_QBC_65-PadL6)") (class "Default")
      (node (ref "U1") (pin "L6") (pinfunction "IO_L13N_T2L_N1_GC_QBC_65_L6") (pintype "bidirectional+no_connect"))
    )
    (net (code "149") (name "unconnected-(U1G-IO_L19N_T3L_N1_DBC_AD9N_65-PadJ4)") (class "Default")
      (node (ref "U1") (pin "J4") (pinfunction "IO_L19N_T3L_N1_DBC_AD9N_65_J4") (pintype "bidirectional+no_connect"))
    )
    (net (code "150") (name "unconnected-(U1G-IO_T0U_N12_VRP_65-PadW9)") (class "Default")
      (node (ref "U1") (pin "W9") (pinfunction "IO_T0U_N12_VRP_65_W9") (pintype "bidirectional+no_connect"))
    )
    (net (code "151") (name "unconnected-(U1G-IO_T1U_N12_65-PadH2)") (class "Default")
      (node (ref "U1") (pin "H2") (pinfunction "IO_T1U_N12_65_H2") (pintype "bidirectional+no_connect"))
    )
    (net (code "152") (name "unconnected-(U1G-IO_T2U_N12_65-PadP9)") (class "Default")
      (node (ref "U1") (pin "P9") (pinfunction "IO_T2U_N12_65_P9") (pintype "bidirectional+no_connect"))
    )
    (net (code "153") (name "unconnected-(U1G-IO_T3U_N12_65-PadK5)") (class "Default")
      (node (ref "U1") (pin "K5") (pinfunction "IO_T3U_N12_65_K5") (pintype "bidirectional+no_connect"))
    )
    (net (code "154") (name "unconnected-(U1H-IO_L11N_T1U_N9_GC_64-PadAF6)") (class "Default")
      (node (ref "U1") (pin "AF6") (pinfunction "IO_L11N_T1U_N9_GC_64_AF6") (pintype "bidirectional+no_connect"))
    )
    (net (code "155") (name "unconnected-(U1H-IO_L11P_T1U_N8_GC_64-PadAF7)") (class "Default")
      (node (ref "U1") (pin "AF7") (pinfunction "IO_L11P_T1U_N8_GC_64_AF7") (pintype "bidirectional+no_connect"))
    )
    (net (code "156") (name "unconnected-(U1H-IO_L18N_T2U_N11_AD2N_64-PadAC1)") (class "Default")
      (node (ref "U1") (pin "AC1") (pinfunction "IO_L18N_T2U_N11_AD2N_64_AC1") (pintype "bidirectional+no_connect"))
    )
    (net (code "157") (name "unconnected-(U1H-IO_L18P_T2U_N10_AD2P_64-PadAB1)") (class "Default")
      (node (ref "U1") (pin "AB1") (pinfunction "IO_L18P_T2U_N10_AD2P_64_AB1") (pintype "bidirectional+no_connect"))
    )
    (net (code "158") (name "unconnected-(U1H-IO_L19N_T3L_N1_DBC_AD9N_64-PadAH4)") (class "Default")
      (node (ref "U1") (pin "AH4") (pinfunction "IO_L19N_T3L_N1_DBC_AD9N_64_AH4") (pintype "bidirectional+no_connect"))
    )
    (net (code "159") (name "unconnected-(U1H-IO_T0U_N12_VRP_64-PadAD6)") (class "Default")
      (node (ref "U1") (pin "AD6") (pinfunction "IO_T0U_N12_VRP_64_AD6") (pintype "bidirectional+no_connect"))
    )
    (net (code "160") (name "unconnected-(U1H-IO_T2U_N12_64-PadAB5)") (class "Default")
      (node (ref "U1") (pin "AB5") (pinfunction "IO_T2U_N12_64_AB5") (pintype "bidirectional+no_connect"))
    )
    (net (code "161") (name "unconnected-(U1H-IO_T3U_N12_64-PadAE4)") (class "Default")
      (node (ref "U1") (pin "AE4") (pinfunction "IO_T3U_N12_64_AE4") (pintype "bidirectional+no_connect"))
    )
  )
)
